# HixCO2TemperatureIRBlaster.net
KiCad netlist of a schematic drawn in EAGLE
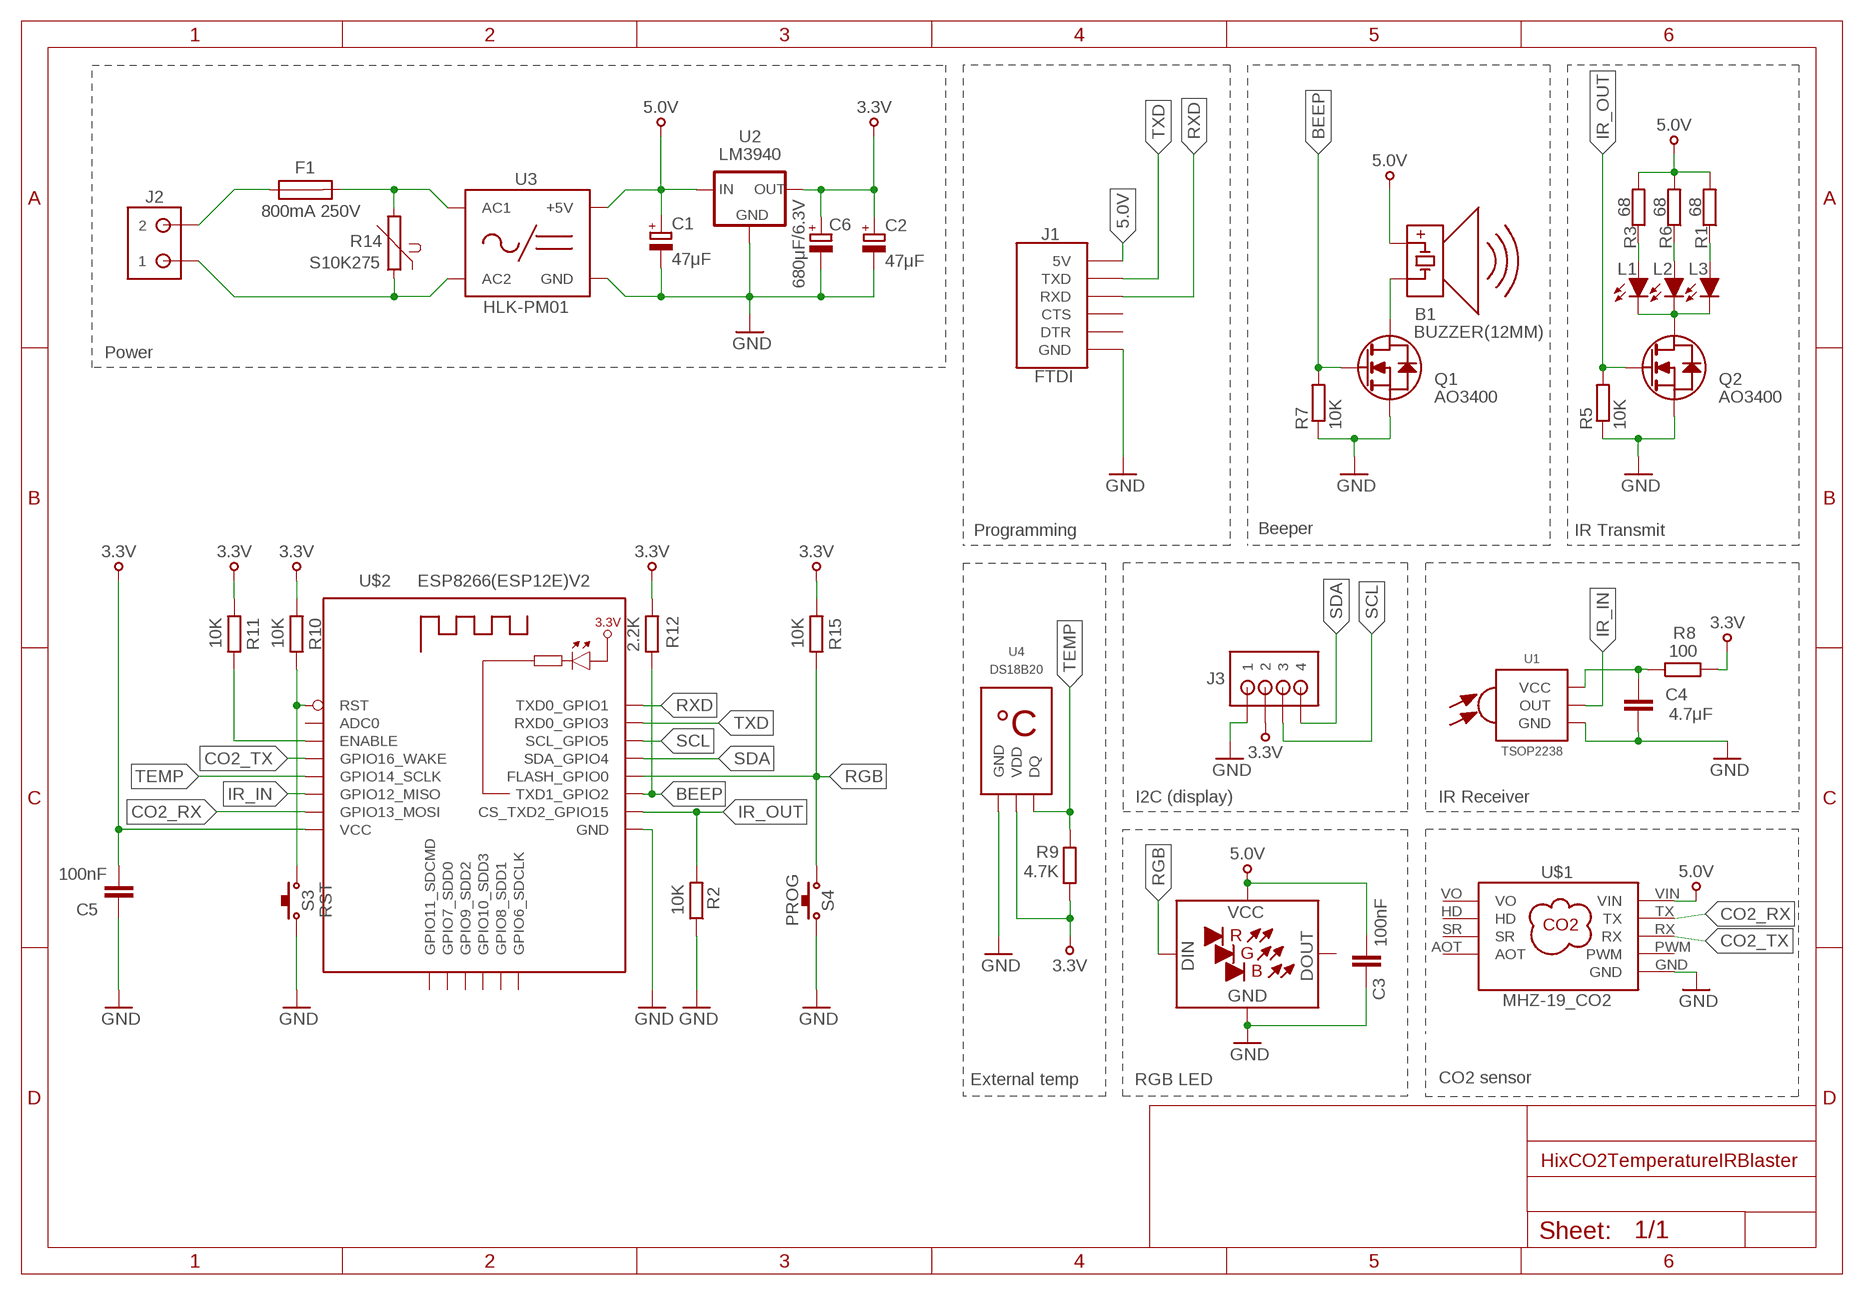
[diagram p0: schematic, sheet 1]

(export (version "E")
  (design (tool "Eeschema 10.0.6"))
  (components
    (comp (ref "B1")
      (value "BUZZER(12MM)")
      (footprint "eagle-import:BUZZER(12MM)")
      (libsource (lib "eagle-import") (part "BUZZER(12MM)"))
    )
    (comp (ref "C1")
      (value "47μF")
      (footprint "eagle-import:SMC_A")
      (libsource (lib "eagle-import") (part "CPOL-EUSMCA"))
    )
    (comp (ref "C2")
      (value "47μF")
      (footprint "eagle-import:SMC_A")
      (libsource (lib "eagle-import") (part "CPOL-EUSMCA"))
    )
    (comp (ref "C3")
      (value "100nF")
      (footprint "eagle-import:C1206")
      (libsource (lib "eagle-import") (part "C-EUC1206"))
    )
    (comp (ref "C4")
      (value "4.7μF")
      (footprint "eagle-import:C1206")
      (libsource (lib "eagle-import") (part "C-EUC1206"))
    )
    (comp (ref "C5")
      (value "100nF")
      (footprint "eagle-import:C1206")
      (fields (field (name "SPICEPREFIX") "C"))
      (libsource (lib "eagle-import") (part "C-EUC1206"))
    )
    (comp (ref "C6")
      (value "680μF/6.3V")
      (footprint "eagle-import:ELKO_RADIAL_STRAIGHT_4P_8D_9H")
      (libsource (lib "eagle-import") (part "ELCOELKO_RADIAL_STRAIGHT_4P_8D_9H"))
    )
    (comp (ref "F1")
      (value "800mA 250V")
      (footprint "eagle-import:FUSE_508")
      (libsource (lib "eagle-import") (part "FUSE"))
    )
    (comp (ref "J1")
      (value "FTDI")
      (footprint "eagle-import:FTDI")
      (libsource (lib "eagle-import") (part "FTDI"))
    )
    (comp (ref "J2")
      (value "IEC320C8")
      (footprint "eagle-import:IEC320C8")
      (libsource (lib "eagle-import") (part "IEC320C8"))
    )
    (comp (ref "J3")
      (value "XH4P")
      (footprint "eagle-import:XH4P")
      (libsource (lib "eagle-import") (part "XH4P"))
    )
    (comp (ref "L1")
      (value "LEDLED5MM_ANGLED1")
      (footprint "eagle-import:LED5MM_ANGLED1")
      (libsource (lib "eagle-import") (part "LEDLED5MM_ANGLED1"))
    )
    (comp (ref "L2")
      (value "LEDLED5MM_ANGLED1")
      (footprint "eagle-import:LED5MM_ANGLED1")
      (libsource (lib "eagle-import") (part "LEDLED5MM_ANGLED1"))
    )
    (comp (ref "L3")
      (value "LEDLED5MM_ANGLED1")
      (footprint "eagle-import:LED5MM_ANGLED1")
      (libsource (lib "eagle-import") (part "LEDLED5MM_ANGLED1"))
    )
    (comp (ref "Q1")
      (value "AO3400")
      (footprint "eagle-import:SOT23")
      (libsource (lib "eagle-import") (part "AO3400"))
    )
    (comp (ref "Q2")
      (value "AO3400")
      (footprint "eagle-import:SOT23")
      (libsource (lib "eagle-import") (part "AO3400"))
    )
    (comp (ref "R1")
      (value "68")
      (footprint "eagle-import:0204_7")
      (libsource (lib "eagle-import") (part "R-EU_0204/7"))
    )
    (comp (ref "R2")
      (value "10K")
      (footprint "eagle-import:R1206")
      (libsource (lib "eagle-import") (part "R-EU_R1206"))
    )
    (comp (ref "R3")
      (value "68")
      (footprint "eagle-import:0204_7")
      (libsource (lib "eagle-import") (part "R-EU_0204/7"))
    )
    (comp (ref "R5")
      (value "10K")
      (footprint "eagle-import:R1206")
      (libsource (lib "eagle-import") (part "R-EU_R1206"))
    )
    (comp (ref "R6")
      (value "68")
      (footprint "eagle-import:0204_7")
      (libsource (lib "eagle-import") (part "R-EU_0204/7"))
    )
    (comp (ref "R7")
      (value "10K")
      (footprint "eagle-import:R1206")
      (libsource (lib "eagle-import") (part "R-EU_R1206"))
    )
    (comp (ref "R8")
      (value "100")
      (footprint "eagle-import:R1206")
      (libsource (lib "eagle-import") (part "R-EU_R1206"))
    )
    (comp (ref "R9")
      (value "4.7K")
      (footprint "eagle-import:R1206")
      (libsource (lib "eagle-import") (part "R-EU_R1206"))
    )
    (comp (ref "R10")
      (value "10K")
      (footprint "eagle-import:R1206")
      (libsource (lib "eagle-import") (part "R-EU_R1206"))
    )
    (comp (ref "R11")
      (value "10K")
      (footprint "eagle-import:R1206")
      (libsource (lib "eagle-import") (part "R-EU_R1206"))
    )
    (comp (ref "R12")
      (value "2.2K")
      (footprint "eagle-import:R1206")
      (libsource (lib "eagle-import") (part "R-EU_R1206"))
    )
    (comp (ref "R14")
      (value "S10K275")
      (footprint "eagle-import:S10K275")
      (libsource (lib "eagle-import") (part "S10K275"))
    )
    (comp (ref "R15")
      (value "10K")
      (footprint "eagle-import:R1206")
      (libsource (lib "eagle-import") (part "R-EU_R1206"))
    )
    (comp (ref "S3")
      (value "RST")
      (footprint "eagle-import:SMDPUSHBTN_TYPE1")
      (libsource (lib "eagle-import") (part "PUSHBTNSMALL"))
    )
    (comp (ref "S4")
      (value "PROG")
      (footprint "eagle-import:SMDPUSHBTN_TYPE1")
      (libsource (lib "eagle-import") (part "PUSHBTNSMALL"))
    )
    (comp (ref "U$1")
      (value "MHZ-19_CO2")
      (footprint "eagle-import:MHZ-19_CO2")
      (libsource (lib "eagle-import") (part "MHZ-19_CO2"))
    )
    (comp (ref "U$2")
      (value "ESP8266(ESP12E)V2")
      (footprint "eagle-import:ESP8266(ESP12E)")
      (libsource (lib "eagle-import") (part "ESP8266(ESP12E)V2"))
    )
    (comp (ref "U$3")
      (value "LED_RGB")
      (footprint "eagle-import:LED_PL9823-F5")
      (libsource (lib "eagle-import") (part "LED_RGB"))
    )
    (comp (ref "U1")
      (value "TSOP2238")
      (footprint "eagle-import:TSOP2238")
      (libsource (lib "eagle-import") (part "TSOP2238"))
    )
    (comp (ref "U2")
      (value "LM3940")
      (footprint "eagle-import:SOT223")
      (libsource (lib "eagle-import") (part "LM3940"))
    )
    (comp (ref "U3")
      (value "HLK-PM01")
      (footprint "eagle-import:HLK-PM01")
      (libsource (lib "eagle-import") (part "HLK-PM01"))
    )
    (comp (ref "U4")
      (value "DS18B20")
      (footprint "eagle-import:TO-92(123)")
      (libsource (lib "eagle-import") (part "DS18B20"))
    )
  )
  (nets
    (net (code "1") (name "/VO") (class "Default")
      (node (ref "U$1") (pin "VO") (pinfunction "VO_VO") (pintype "power_in"))
    )
    (net (code "2") (name "3.3V") (class "Default")
      (node (ref "C2") (pin "+") (pinfunction "+_+") (pintype "passive"))
      (node (ref "C5") (pin "1") (pinfunction "1_1") (pintype "passive"))
      (node (ref "C6") (pin "+") (pinfunction "+_+") (pintype "passive"))
      (node (ref "J3") (pin "2") (pinfunction "2_2") (pintype "bidirectional"))
      (node (ref "R10") (pin "2") (pinfunction "2_2") (pintype "passive"))
      (node (ref "R11") (pin "2") (pinfunction "2_2") (pintype "passive"))
      (node (ref "R12") (pin "2") (pinfunction "2_2") (pintype "passive"))
      (node (ref "R15") (pin "2") (pinfunction "2_2") (pintype "passive"))
      (node (ref "R8") (pin "2") (pinfunction "2_2") (pintype "passive"))
      (node (ref "R9") (pin "2") (pinfunction "2_2") (pintype "passive"))
      (node (ref "U$2") (pin "VCC") (pinfunction "VCC_VCC") (pintype "power_in"))
      (node (ref "U2") (pin "3") (pinfunction "OUT_3") (pintype "power_in"))
      (node (ref "U4") (pin "3") (pinfunction "VDD_3") (pintype "power_in"))
    )
    (net (code "3") (name "5.0V") (class "Default")
      (node (ref "B1") (pin "+") (pinfunction "+_+") (pintype "input"))
      (node (ref "C1") (pin "+") (pinfunction "+_+") (pintype "passive"))
      (node (ref "C3") (pin "1") (pinfunction "1_1") (pintype "passive"))
      (node (ref "J1") (pin "5V") (pinfunction "5V_5V") (pintype "bidirectional"))
      (node (ref "R1") (pin "2") (pinfunction "2_2") (pintype "passive"))
      (node (ref "R3") (pin "2") (pinfunction "2_2") (pintype "passive"))
      (node (ref "R6") (pin "2") (pinfunction "2_2") (pintype "passive"))
      (node (ref "U$1") (pin "VIN") (pinfunction "VIN_VIN") (pintype "power_in"))
      (node (ref "U$3") (pin "VCC") (pinfunction "VCC_VCC") (pintype "bidirectional"))
      (node (ref "U2") (pin "1") (pinfunction "IN_1") (pintype "input"))
      (node (ref "U3") (pin "VO+") (pinfunction "+5V_VO+") (pintype "power_in"))
    )
    (net (code "4") (name "BEEP") (class "Default")
      (node (ref "Q1") (pin "1") (pinfunction "G_1") (pintype "bidirectional"))
      (node (ref "R12") (pin "1") (pinfunction "1_1") (pintype "passive"))
      (node (ref "R7") (pin "2") (pinfunction "2_2") (pintype "passive"))
      (node (ref "U$2") (pin "GPIO2_TXD1") (pinfunction "TXD1_GPIO2_GPIO2_TXD1") (pintype "bidirectional"))
    )
    (net (code "5") (name "CO2_RX") (class "Default")
      (node (ref "U$1") (pin "TX") (pinfunction "TX_TX") (pintype "output"))
      (node (ref "U$2") (pin "GPIO13_MOSI") (pinfunction "GPIO13_MOSI_GPIO13_MOSI") (pintype "bidirectional"))
    )
    (net (code "6") (name "CO2_TX") (class "Default")
      (node (ref "U$1") (pin "RX") (pinfunction "RX_RX") (pintype "input"))
      (node (ref "U$2") (pin "GPIO16_WAKE") (pinfunction "GPIO16_WAKE_GPIO16_WAKE") (pintype "bidirectional"))
    )
    (net (code "7") (name "GND") (class "Default")
      (node (ref "C1") (pin "-") (pinfunction "-_-") (pintype "passive"))
      (node (ref "C2") (pin "-") (pinfunction "-_-") (pintype "passive"))
      (node (ref "C3") (pin "2") (pinfunction "2_2") (pintype "passive"))
      (node (ref "C4") (pin "2") (pinfunction "2_2") (pintype "passive"))
      (node (ref "C5") (pin "2") (pinfunction "2_2") (pintype "passive"))
      (node (ref "C6") (pin "-") (pinfunction "-_-") (pintype "passive"))
      (node (ref "J1") (pin "GND") (pinfunction "GND_GND") (pintype "bidirectional"))
      (node (ref "J3") (pin "1") (pinfunction "1_1") (pintype "bidirectional"))
      (node (ref "Q1") (pin "2") (pinfunction "S_2") (pintype "bidirectional"))
      (node (ref "Q2") (pin "2") (pinfunction "S_2") (pintype "bidirectional"))
      (node (ref "R2") (pin "1") (pinfunction "1_1") (pintype "passive"))
      (node (ref "R5") (pin "1") (pinfunction "1_1") (pintype "passive"))
      (node (ref "R7") (pin "1") (pinfunction "1_1") (pintype "passive"))
      (node (ref "S3") (pin "2") (pinfunction "2_2") (pintype "passive"))
      (node (ref "S4") (pin "2") (pinfunction "2_2") (pintype "passive"))
      (node (ref "U$1") (pin "GND") (pinfunction "GND_GND") (pintype "power_in"))
      (node (ref "U$2") (pin "GND") (pinfunction "GND_GND") (pintype "power_in"))
      (node (ref "U$3") (pin "GND") (pinfunction "GND_GND") (pintype "power_in"))
      (node (ref "U1") (pin "GND") (pinfunction "GND_GND") (pintype "bidirectional"))
      (node (ref "U2") (pin "2") (pinfunction "GND_2") (pintype "input"))
      (node (ref "U2") (pin "4") (pinfunction "GND_4") (pintype "input"))
      (node (ref "U3") (pin "VO-") (pinfunction "GND_VO-") (pintype "power_in"))
      (node (ref "U4") (pin "1") (pinfunction "GND_1") (pintype "power_in"))
    )
    (net (code "8") (name "IR_IN") (class "Default")
      (node (ref "U$2") (pin "GPIO12_MISO") (pinfunction "GPIO12_MISO_GPIO12_MISO") (pintype "bidirectional"))
      (node (ref "U1") (pin "OUT") (pinfunction "OUT_OUT") (pintype "bidirectional"))
    )
    (net (code "9") (name "IR_OUT") (class "Default")
      (node (ref "Q2") (pin "1") (pinfunction "G_1") (pintype "bidirectional"))
      (node (ref "R2") (pin "2") (pinfunction "2_2") (pintype "passive"))
      (node (ref "R5") (pin "2") (pinfunction "2_2") (pintype "passive"))
      (node (ref "U$2") (pin "GPIO15_CS_TXD2") (pinfunction "CS_TXD2_GPIO15_GPIO15_CS_TXD2") (pintype "bidirectional"))
    )
    (net (code "10") (name "Net-(C4-Pad1)") (class "Default")
      (node (ref "C4") (pin "1") (pinfunction "1_1") (pintype "passive"))
      (node (ref "R8") (pin "1") (pinfunction "1_1") (pintype "passive"))
      (node (ref "U1") (pin "VCC") (pinfunction "VCC_VCC") (pintype "bidirectional"))
    )
    (net (code "11") (name "Net-(F1-Pad2)") (class "Default")
      (node (ref "F1") (pin "2") (pinfunction "2_2") (pintype "passive"))
      (node (ref "R14") (pin "2") (pinfunction "2_2") (pintype "passive"))
      (node (ref "U3") (pin "AC1") (pinfunction "AC1_AC1") (pintype "input"))
    )
    (net (code "12") (name "Net-(J2-1)") (class "Default")
      (node (ref "J2") (pin "AC1") (pinfunction "1_AC1") (pintype "bidirectional"))
      (node (ref "R14") (pin "1") (pinfunction "1_1") (pintype "passive"))
      (node (ref "U3") (pin "AC2") (pinfunction "AC2_AC2") (pintype "input"))
    )
    (net (code "13") (name "Net-(J2-2)") (class "Default")
      (node (ref "F1") (pin "1") (pinfunction "1_1") (pintype "passive"))
      (node (ref "J2") (pin "AC2") (pinfunction "2_AC2") (pintype "bidirectional"))
    )
    (net (code "14") (name "Net-(L1-A)") (class "Default")
      (node (ref "L1") (pin "ANODE") (pinfunction "A_ANODE") (pintype "passive"))
      (node (ref "R3") (pin "1") (pinfunction "1_1") (pintype "passive"))
    )
    (net (code "15") (name "Net-(L1-C)") (class "Default")
      (node (ref "L1") (pin "CATHODE") (pinfunction "C_CATHODE") (pintype "passive"))
      (node (ref "L2") (pin "CATHODE") (pinfunction "C_CATHODE") (pintype "passive"))
      (node (ref "L3") (pin "CATHODE") (pinfunction "C_CATHODE") (pintype "passive"))
      (node (ref "Q2") (pin "3") (pinfunction "D_3") (pintype "bidirectional"))
    )
    (net (code "16") (name "Net-(L2-A)") (class "Default")
      (node (ref "L2") (pin "ANODE") (pinfunction "A_ANODE") (pintype "passive"))
      (node (ref "R6") (pin "1") (pinfunction "1_1") (pintype "passive"))
    )
    (net (code "17") (name "Net-(L3-A)") (class "Default")
      (node (ref "L3") (pin "ANODE") (pinfunction "A_ANODE") (pintype "passive"))
      (node (ref "R1") (pin "1") (pinfunction "1_1") (pintype "passive"))
    )
    (net (code "18") (name "Net-(Q1-D)") (class "Default")
      (node (ref "B1") (pin "-") (pinfunction "-_-") (pintype "input"))
      (node (ref "Q1") (pin "3") (pinfunction "D_3") (pintype "bidirectional"))
    )
    (net (code "19") (name "Net-(R10-Pad1)") (class "Default")
      (node (ref "R10") (pin "1") (pinfunction "1_1") (pintype "passive"))
      (node (ref "S3") (pin "1") (pinfunction "1_1") (pintype "passive"))
      (node (ref "U$2") (pin "RST") (pinfunction "RST_RST") (pintype "input"))
    )
    (net (code "20") (name "Net-(R11-Pad1)") (class "Default")
      (node (ref "R11") (pin "1") (pinfunction "1_1") (pintype "passive"))
      (node (ref "U$2") (pin "ENABLE") (pinfunction "ENABLE_ENABLE") (pintype "input"))
    )
    (net (code "21") (name "RGB") (class "Default")
      (node (ref "R15") (pin "1") (pinfunction "1_1") (pintype "passive"))
      (node (ref "S4") (pin "1") (pinfunction "1_1") (pintype "passive"))
      (node (ref "U$2") (pin "GPIO0_FLASH") (pinfunction "FLASH_GPIO0_GPIO0_FLASH") (pintype "bidirectional"))
      (node (ref "U$3") (pin "DIN") (pinfunction "DIN_DIN") (pintype "input"))
    )
    (net (code "22") (name "RXD") (class "Default")
      (node (ref "J1") (pin "RXD") (pinfunction "RXD_RXD") (pintype "bidirectional"))
      (node (ref "U$2") (pin "GPIO1_TXD0") (pinfunction "TXD0_GPIO1_GPIO1_TXD0") (pintype "bidirectional"))
    )
    (net (code "23") (name "SCL") (class "Default")
      (node (ref "J3") (pin "3") (pinfunction "3_3") (pintype "bidirectional"))
      (node (ref "U$2") (pin "GPIO5_SCL") (pinfunction "SCL_GPIO5_GPIO5_SCL") (pintype "bidirectional"))
    )
    (net (code "24") (name "SDA") (class "Default")
      (node (ref "J3") (pin "4") (pinfunction "4_4") (pintype "bidirectional"))
      (node (ref "U$2") (pin "GPIO4_SDA") (pinfunction "SDA_GPIO4_GPIO4_SDA") (pintype "bidirectional"))
    )
    (net (code "25") (name "TEMP") (class "Default")
      (node (ref "R9") (pin "1") (pinfunction "1_1") (pintype "passive"))
      (node (ref "U$2") (pin "GPIO14_SCLK") (pinfunction "GPIO14_SCLK_GPIO14_SCLK") (pintype "bidirectional"))
      (node (ref "U4") (pin "2") (pinfunction "DQ_2") (pintype "bidirectional"))
    )
    (net (code "26") (name "TXD") (class "Default")
      (node (ref "J1") (pin "TXD") (pinfunction "TXD_TXD") (pintype "bidirectional"))
      (node (ref "U$2") (pin "GPIO3_RXD0") (pinfunction "RXD0_GPIO3_GPIO3_RXD0") (pintype "input"))
    )
    (net (code "27") (name "unconnected-(J1-PadCTS)") (class "Default")
      (node (ref "J1") (pin "CTS") (pinfunction "CTS_CTS") (pintype "bidirectional"))
    )
    (net (code "28") (name "unconnected-(J1-PadDTR)") (class "Default")
      (node (ref "J1") (pin "DTR") (pinfunction "DTR_DTR") (pintype "bidirectional"))
    )
    (net (code "29") (name "unconnected-(U$1-PadAOT)") (class "Default")
      (node (ref "U$1") (pin "AOT") (pinfunction "AOT_AOT") (pintype "no_connect"))
    )
    (net (code "30") (name "unconnected-(U$1-PadHD)") (class "Default")
      (node (ref "U$1") (pin "HD") (pinfunction "HD_HD") (pintype "no_connect"))
    )
    (net (code "31") (name "unconnected-(U$1-PadPWM)") (class "Default")
      (node (ref "U$1") (pin "PWM") (pinfunction "PWM_PWM") (pintype "output"))
    )
    (net (code "32") (name "unconnected-(U$1-PadSR)") (class "Default")
      (node (ref "U$1") (pin "SR") (pinfunction "SR_SR") (pintype "no_connect"))
    )
    (net (code "33") (name "unconnected-(U$2-GPIO11_SDCMD-PadCPIO11_SDCMD)") (class "Default")
      (node (ref "U$2") (pin "CPIO11_SDCMD") (pinfunction "GPIO11_SDCMD_CPIO11_SDCMD") (pintype "no_connect"))
    )
    (net (code "34") (name "unconnected-(U$2-PadADC0)") (class "Default")
      (node (ref "U$2") (pin "ADC0") (pinfunction "ADC0_ADC0") (pintype "input"))
    )
    (net (code "35") (name "unconnected-(U$2-PadGPIO6_SDCLK)") (class "Default")
      (node (ref "U$2") (pin "GPIO6_SDCLK") (pinfunction "GPIO6_SDCLK_GPIO6_SDCLK") (pintype "no_connect"))
    )
    (net (code "36") (name "unconnected-(U$2-PadGPIO7_SDD0)") (class "Default")
      (node (ref "U$2") (pin "GPIO7_SDD0") (pinfunction "GPIO7_SDD0_GPIO7_SDD0") (pintype "no_connect"))
    )
    (net (code "37") (name "unconnected-(U$2-PadGPIO8_SDD1)") (class "Default")
      (node (ref "U$2") (pin "GPIO8_SDD1") (pinfunction "GPIO8_SDD1_GPIO8_SDD1") (pintype "no_connect"))
    )
    (net (code "38") (name "unconnected-(U$2-PadGPIO9_SDD2)") (class "Default")
      (node (ref "U$2") (pin "GPIO9_SDD2") (pinfunction "GPIO9_SDD2_GPIO9_SDD2") (pintype "no_connect"))
    )
    (net (code "39") (name "unconnected-(U$2-PadGPIO10_SDD3)") (class "Default")
      (node (ref "U$2") (pin "GPIO10_SDD3") (pinfunction "GPIO10_SDD3_GPIO10_SDD3") (pintype "no_connect"))
    )
    (net (code "40") (name "unconnected-(U$3-PadDOUT)") (class "Default")
      (node (ref "U$3") (pin "DOUT") (pinfunction "DOUT_DOUT") (pintype "output"))
    )
  )
)
